# ghf_sensor.net
KiCad netlist of a schematic drawn in EAGLE
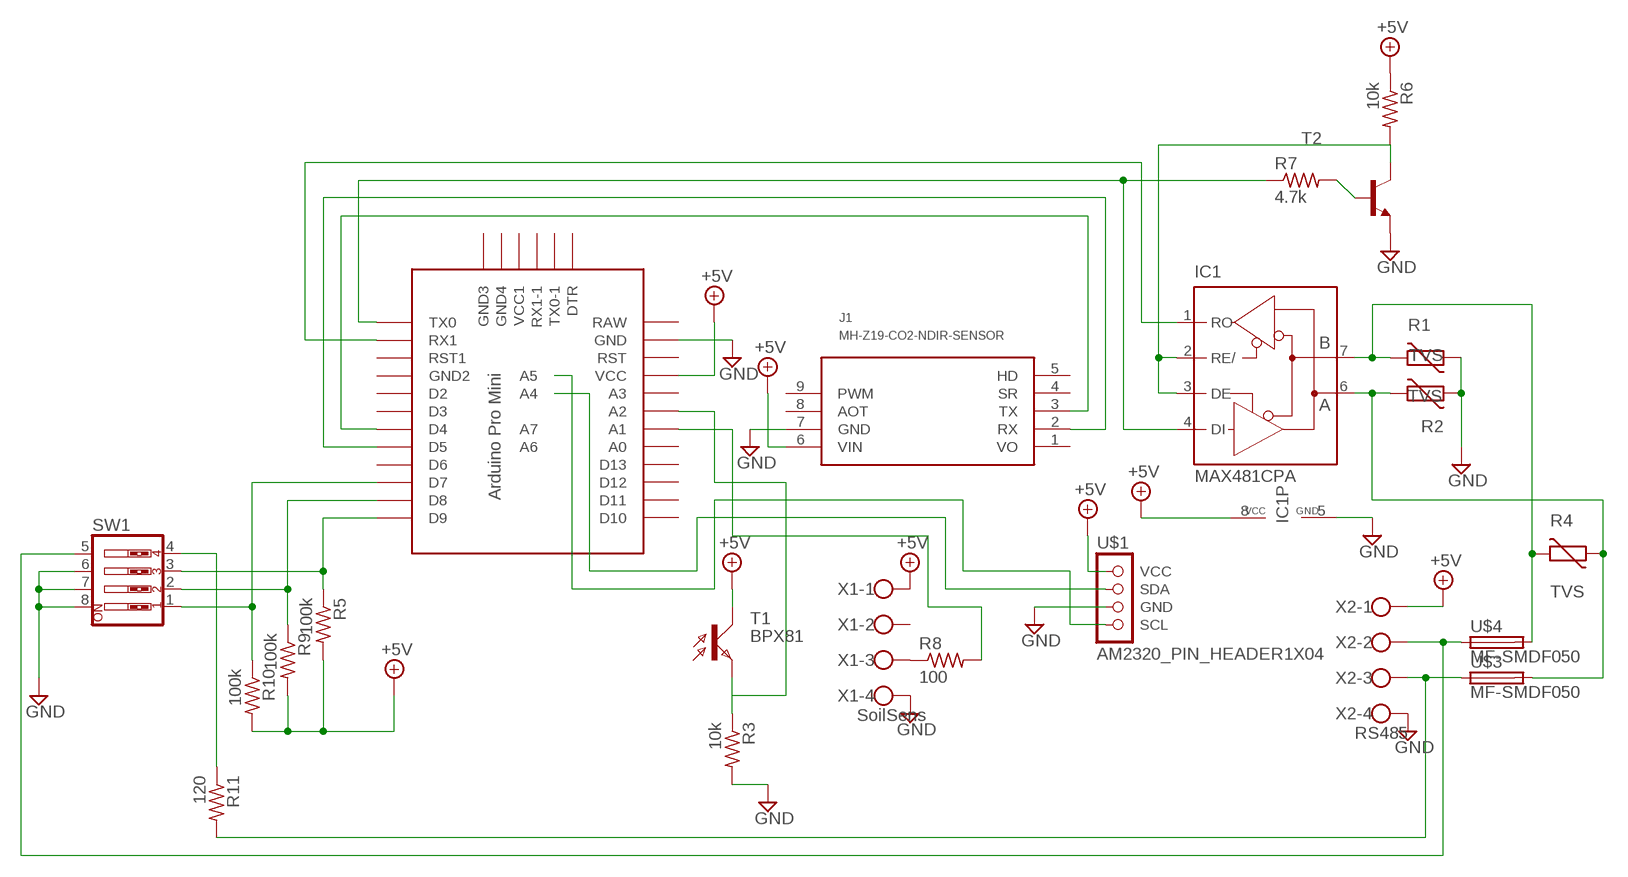
[diagram p0: schematic, sheet 1]

(export (version "E")
  (design (tool "Eeschema 10.0.6"))
  (components
    (comp (ref "IC1")
      (value "MAX481CPA")
      (footprint "eagle-import:DIL08")
      (libsource (lib "eagle-import") (part "MAX481CPA"))
    )
    (comp (ref "J1")
      (value "MH-Z19-CO2-NDIR-SENSOR")
      (footprint "eagle-import:MH-Z19")
      (libsource (lib "eagle-import") (part "MH-Z19-CO2-NDIR-SENSOR"))
    )
    (comp (ref "R1")
      (value "TVS")
      (footprint "eagle-import:CT_CN1812")
      (libsource (lib "eagle-import") (part "VARISTORCN1812"))
    )
    (comp (ref "R2")
      (value "TVS")
      (footprint "eagle-import:CT_CN1812")
      (libsource (lib "eagle-import") (part "VARISTORCN1812"))
    )
    (comp (ref "R3")
      (value "10k")
      (footprint "eagle-import:0204_5")
      (libsource (lib "eagle-import") (part "R-US_0204/5"))
    )
    (comp (ref "R4")
      (value "TVS")
      (footprint "eagle-import:CT_CN1812")
      (libsource (lib "eagle-import") (part "VARISTORCN1812"))
    )
    (comp (ref "R5")
      (value "100k")
      (footprint "eagle-import:0204V")
      (libsource (lib "eagle-import") (part "R-US_0204/2V"))
    )
    (comp (ref "R6")
      (value "10k")
      (footprint "eagle-import:0204_5")
      (libsource (lib "eagle-import") (part "R-US_0204/5"))
    )
    (comp (ref "R7")
      (value "4.7k")
      (footprint "eagle-import:0204_5")
      (libsource (lib "eagle-import") (part "R-US_0204/5"))
    )
    (comp (ref "R8")
      (value "100")
      (footprint "eagle-import:0204_5")
      (libsource (lib "eagle-import") (part "R-US_0204/5"))
    )
    (comp (ref "R9")
      (value "100k")
      (footprint "eagle-import:0204V")
      (libsource (lib "eagle-import") (part "R-US_0204/2V"))
    )
    (comp (ref "R10")
      (value "100k")
      (footprint "eagle-import:0204V")
      (libsource (lib "eagle-import") (part "R-US_0204/2V"))
    )
    (comp (ref "R11")
      (value "120")
      (footprint "eagle-import:0204V")
      (libsource (lib "eagle-import") (part "R-US_0204/2V"))
    )
    (comp (ref "SW1")
      (value "SW_DIP-4")
      (footprint "eagle-import:EDG-04")
      (libsource (lib "eagle-import") (part "SW_DIP-4"))
    )
    (comp (ref "T1")
      (value "BPX81")
      (footprint "eagle-import:BPX81")
      (libsource (lib "eagle-import") (part "BPX81"))
    )
    (comp (ref "T2")
      (value "-NPN-TO92-ECB")
      (footprint "eagle-import:TO92-ECB")
      (libsource (lib "eagle-import") (part "-NPN-TO92-ECB"))
    )
    (comp (ref "U$1")
      (value "AM2320_PIN_HEADER1X04")
      (footprint "eagle-import:1X04")
      (libsource (lib "eagle-import") (part "AM2320_PIN_HEADER1X04"))
    )
    (comp (ref "U$2")
      (value "PRO-MINI-2")
      (footprint "eagle-import:PRO-MINI-2")
      (libsource (lib "eagle-import") (part "PRO-MINI-2"))
    )
    (comp (ref "U$3")
      (value "MF-SMDF050")
      (footprint "eagle-import:MF-SMDF050")
      (libsource (lib "eagle-import") (part "MF-SMDF050"))
    )
    (comp (ref "U$4")
      (value "MF-SMDF050")
      (footprint "eagle-import:MF-SMDF050")
      (libsource (lib "eagle-import") (part "MF-SMDF050"))
    )
    (comp (ref "X1")
      (value "SoilSens")
      (footprint "eagle-import:W237-4")
      (libsource (lib "eagle-import") (part "W237-4"))
    )
    (comp (ref "X2")
      (value "RS485")
      (footprint "eagle-import:W237-4")
      (libsource (lib "eagle-import") (part "W237-4"))
    )
  )
  (nets
    (net (code "1") (name "+5V") (class "Default")
      (node (ref "IC1") (pin "8") (pinfunction "VCC_8") (pintype "power_in"))
      (node (ref "J1") (pin "6") (pinfunction "VIN_6") (pintype "power_in"))
      (node (ref "R10") (pin "2") (pinfunction "2_2") (pintype "passive"))
      (node (ref "R5") (pin "2") (pinfunction "2_2") (pintype "passive"))
      (node (ref "R6") (pin "1") (pinfunction "1_1") (pintype "passive"))
      (node (ref "R9") (pin "2") (pinfunction "2_2") (pintype "passive"))
      (node (ref "T1") (pin "C") (pinfunction "C_C") (pintype "passive"))
      (node (ref "U$1") (pin "1") (pinfunction "VCC_1") (pintype "passive"))
      (node (ref "U$2") (pin "VCC") (pinfunction "VCC_VCC") (pintype "bidirectional"))
      (node (ref "X1") (pin "1") (pinfunction "KL_1") (pintype "passive"))
      (node (ref "X2") (pin "1") (pinfunction "KL_1") (pintype "passive"))
    )
    (net (code "2") (name "/VO") (class "Default")
      (node (ref "J1") (pin "1") (pinfunction "VO_1") (pintype "power_in"))
    )
    (net (code "3") (name "GND") (class "Default")
      (node (ref "IC1") (pin "5") (pinfunction "GND_5") (pintype "power_in"))
      (node (ref "J1") (pin "7") (pinfunction "GND_7") (pintype "power_in"))
      (node (ref "R1") (pin "1") (pinfunction "1_1") (pintype "passive"))
      (node (ref "R2") (pin "2") (pinfunction "2_2") (pintype "passive"))
      (node (ref "R3") (pin "2") (pinfunction "2_2") (pintype "passive"))
      (node (ref "SW1") (pin "6") (pinfunction "6_6") (pintype "passive"))
      (node (ref "SW1") (pin "7") (pinfunction "7_7") (pintype "passive"))
      (node (ref "SW1") (pin "8") (pinfunction "8_8") (pintype "passive"))
      (node (ref "T2") (pin "E") (pinfunction "E_E") (pintype "passive"))
      (node (ref "U$1") (pin "3") (pinfunction "GND_3") (pintype "passive"))
      (node (ref "U$2") (pin "GND") (pinfunction "GND_GND") (pintype "bidirectional"))
      (node (ref "X1") (pin "4") (pinfunction "KL_4") (pintype "passive"))
      (node (ref "X2") (pin "4") (pinfunction "KL_4") (pintype "passive"))
    )
    (net (code "4") (name "Net-(IC1A-A)") (class "Default")
      (node (ref "IC1") (pin "6") (pinfunction "A_6") (pintype "passive"))
      (node (ref "R2") (pin "1") (pinfunction "1_1") (pintype "passive"))
      (node (ref "R4") (pin "1") (pinfunction "1_1") (pintype "passive"))
      (node (ref "U$3") (pin "2") (pinfunction "2_2") (pintype "passive"))
    )
    (net (code "5") (name "Net-(IC1A-B)") (class "Default")
      (node (ref "IC1") (pin "7") (pinfunction "B_7") (pintype "passive"))
      (node (ref "R1") (pin "2") (pinfunction "2_2") (pintype "passive"))
      (node (ref "R4") (pin "2") (pinfunction "2_2") (pintype "passive"))
      (node (ref "U$4") (pin "2") (pinfunction "2_2") (pintype "passive"))
    )
    (net (code "6") (name "Net-(IC1A-DE)") (class "Default")
      (node (ref "IC1") (pin "2") (pinfunction "RE/_2") (pintype "input"))
      (node (ref "IC1") (pin "3") (pinfunction "DE_3") (pintype "input"))
      (node (ref "R6") (pin "2") (pinfunction "2_2") (pintype "passive"))
      (node (ref "T2") (pin "C") (pinfunction "C_C") (pintype "passive"))
    )
    (net (code "7") (name "Net-(IC1A-DI)") (class "Default")
      (node (ref "IC1") (pin "4") (pinfunction "DI_4") (pintype "input"))
      (node (ref "R7") (pin "1") (pinfunction "1_1") (pintype "passive"))
      (node (ref "U$2") (pin "TX0") (pinfunction "TX0_TX0") (pintype "bidirectional"))
    )
    (net (code "8") (name "Net-(IC1A-RO)") (class "Default")
      (node (ref "IC1") (pin "1") (pinfunction "RO_1") (pintype "output"))
      (node (ref "U$2") (pin "RX1") (pinfunction "RX1_RX1") (pintype "bidirectional"))
    )
    (net (code "9") (name "Net-(J1-RX)") (class "Default")
      (node (ref "J1") (pin "2") (pinfunction "RX_2") (pintype "input"))
      (node (ref "U$2") (pin "D5") (pinfunction "D5_D5") (pintype "bidirectional"))
    )
    (net (code "10") (name "Net-(J1-TX)") (class "Default")
      (node (ref "J1") (pin "3") (pinfunction "TX_3") (pintype "output"))
      (node (ref "U$2") (pin "D4") (pinfunction "D4_D4") (pintype "bidirectional"))
    )
    (net (code "11") (name "Net-(R3-Pad1)") (class "Default")
      (node (ref "R3") (pin "1") (pinfunction "1_1") (pintype "passive"))
      (node (ref "T1") (pin "E") (pinfunction "E_E") (pintype "passive"))
      (node (ref "U$2") (pin "A2") (pinfunction "A2_A2") (pintype "bidirectional"))
    )
    (net (code "12") (name "Net-(R5-Pad1)") (class "Default")
      (node (ref "R5") (pin "1") (pinfunction "1_1") (pintype "passive"))
      (node (ref "SW1") (pin "3") (pinfunction "3_3") (pintype "passive"))
      (node (ref "U$2") (pin "D9") (pinfunction "D9_D9") (pintype "bidirectional"))
    )
    (net (code "13") (name "Net-(R7-Pad2)") (class "Default")
      (node (ref "R7") (pin "2") (pinfunction "2_2") (pintype "passive"))
      (node (ref "T2") (pin "B") (pinfunction "B_B") (pintype "passive"))
    )
    (net (code "14") (name "Net-(R8-Pad2)") (class "Default")
      (node (ref "R8") (pin "2") (pinfunction "2_2") (pintype "passive"))
      (node (ref "U$2") (pin "A1") (pinfunction "A1_A1") (pintype "bidirectional"))
    )
    (net (code "15") (name "Net-(R9-Pad1)") (class "Default")
      (node (ref "R9") (pin "1") (pinfunction "1_1") (pintype "passive"))
      (node (ref "SW1") (pin "2") (pinfunction "2_2") (pintype "passive"))
      (node (ref "U$2") (pin "D8") (pinfunction "D8_D8") (pintype "bidirectional"))
    )
    (net (code "16") (name "Net-(R10-Pad1)") (class "Default")
      (node (ref "R10") (pin "1") (pinfunction "1_1") (pintype "passive"))
      (node (ref "SW1") (pin "1") (pinfunction "1_1") (pintype "passive"))
      (node (ref "U$2") (pin "D7") (pinfunction "D7_D7") (pintype "bidirectional"))
    )
    (net (code "17") (name "Net-(R11-Pad1)") (class "Default")
      (node (ref "R11") (pin "1") (pinfunction "1_1") (pintype "passive"))
      (node (ref "SW1") (pin "4") (pinfunction "4_4") (pintype "passive"))
    )
    (net (code "18") (name "Net-(U$1-SCL)") (class "Default")
      (node (ref "U$1") (pin "4") (pinfunction "SCL_4") (pintype "passive"))
      (node (ref "U$2") (pin "A5") (pinfunction "A5_A5") (pintype "bidirectional"))
    )
    (net (code "19") (name "Net-(U$1-SDA)") (class "Default")
      (node (ref "U$1") (pin "2") (pinfunction "SDA_2") (pintype "passive"))
      (node (ref "U$2") (pin "A4") (pinfunction "A4_A4") (pintype "bidirectional"))
    )
    (net (code "20") (name "Net-(X1C-KL)") (class "Default")
      (node (ref "R8") (pin "1") (pinfunction "1_1") (pintype "passive"))
      (node (ref "X1") (pin "3") (pinfunction "KL_3") (pintype "passive"))
    )
    (net (code "21") (name "Net-(X2B-KL)") (class "Default")
      (node (ref "SW1") (pin "5") (pinfunction "5_5") (pintype "passive"))
      (node (ref "U$4") (pin "1") (pinfunction "1_1") (pintype "passive"))
      (node (ref "X2") (pin "2") (pinfunction "KL_2") (pintype "passive"))
    )
    (net (code "22") (name "Net-(X2C-KL)") (class "Default")
      (node (ref "R11") (pin "2") (pinfunction "2_2") (pintype "passive"))
      (node (ref "U$3") (pin "1") (pinfunction "1_1") (pintype "passive"))
      (node (ref "X2") (pin "3") (pinfunction "KL_3") (pintype "passive"))
    )
    (net (code "23") (name "unconnected-(J1-AOT-Pad8)") (class "Default")
      (node (ref "J1") (pin "8") (pinfunction "AOT_8") (pintype "no_connect"))
    )
    (net (code "24") (name "unconnected-(J1-HD-Pad5)") (class "Default")
      (node (ref "J1") (pin "5") (pinfunction "HD_5") (pintype "input"))
    )
    (net (code "25") (name "unconnected-(J1-PWM-Pad9)") (class "Default")
      (node (ref "J1") (pin "9") (pinfunction "PWM_9") (pintype "output"))
    )
    (net (code "26") (name "unconnected-(J1-SR-Pad4)") (class "Default")
      (node (ref "J1") (pin "4") (pinfunction "SR_4") (pintype "no_connect"))
    )
    (net (code "27") (name "unconnected-(U$2-GND2-PadGND1)") (class "Default")
      (node (ref "U$2") (pin "GND1") (pinfunction "GND2_GND1") (pintype "bidirectional"))
    )
    (net (code "28") (name "unconnected-(U$2-GND3-PadGND2)") (class "Default")
      (node (ref "U$2") (pin "GND2") (pinfunction "GND3_GND2") (pintype "bidirectional"))
    )
    (net (code "29") (name "unconnected-(U$2-GND4-PadGND3)") (class "Default")
      (node (ref "U$2") (pin "GND3") (pinfunction "GND4_GND3") (pintype "bidirectional"))
    )
    (net (code "30") (name "unconnected-(U$2-PadA0)") (class "Default")
      (node (ref "U$2") (pin "A0") (pinfunction "A0_A0") (pintype "bidirectional"))
    )
    (net (code "31") (name "unconnected-(U$2-PadA3)") (class "Default")
      (node (ref "U$2") (pin "A3") (pinfunction "A3_A3") (pintype "bidirectional"))
    )
    (net (code "32") (name "unconnected-(U$2-PadA6)") (class "Default")
      (node (ref "U$2") (pin "A6") (pinfunction "A6_A6") (pintype "bidirectional"))
    )
    (net (code "33") (name "unconnected-(U$2-PadA7)") (class "Default")
      (node (ref "U$2") (pin "A7") (pinfunction "A7_A7") (pintype "bidirectional"))
    )
    (net (code "34") (name "unconnected-(U$2-PadD2)") (class "Default")
      (node (ref "U$2") (pin "D2") (pinfunction "D2_D2") (pintype "bidirectional"))
    )
    (net (code "35") (name "unconnected-(U$2-PadD3)") (class "Default")
      (node (ref "U$2") (pin "D3") (pinfunction "D3_D3") (pintype "bidirectional"))
    )
    (net (code "36") (name "unconnected-(U$2-PadD6)") (class "Default")
      (node (ref "U$2") (pin "D6") (pinfunction "D6_D6") (pintype "bidirectional"))
    )
    (net (code "37") (name "unconnected-(U$2-PadD10)") (class "Default")
      (node (ref "U$2") (pin "D10") (pinfunction "D10_D10") (pintype "bidirectional"))
    )
    (net (code "38") (name "unconnected-(U$2-PadD11)") (class "Default")
      (node (ref "U$2") (pin "D11") (pinfunction "D11_D11") (pintype "bidirectional"))
    )
    (net (code "39") (name "unconnected-(U$2-PadD12)") (class "Default")
      (node (ref "U$2") (pin "D12") (pinfunction "D12_D12") (pintype "bidirectional"))
    )
    (net (code "40") (name "unconnected-(U$2-PadD13)") (class "Default")
      (node (ref "U$2") (pin "D13") (pinfunction "D13_D13") (pintype "bidirectional"))
    )
    (net (code "41") (name "unconnected-(U$2-PadDTR)") (class "Default")
      (node (ref "U$2") (pin "DTR") (pinfunction "DTR_DTR") (pintype "bidirectional"))
    )
    (net (code "42") (name "unconnected-(U$2-PadRAW)") (class "Default")
      (node (ref "U$2") (pin "RAW") (pinfunction "RAW_RAW") (pintype "bidirectional"))
    )
    (net (code "43") (name "unconnected-(U$2-PadRST)") (class "Default")
      (node (ref "U$2") (pin "RST") (pinfunction "RST_RST") (pintype "bidirectional"))
    )
    (net (code "44") (name "unconnected-(U$2-PadRST1)") (class "Default")
      (node (ref "U$2") (pin "RST1") (pinfunction "RST1_RST1") (pintype "bidirectional"))
    )
    (net (code "45") (name "unconnected-(U$2-PadRX1-1)") (class "Default")
      (node (ref "U$2") (pin "RX1-1") (pinfunction "RX1-1_RX1-1") (pintype "bidirectional"))
    )
    (net (code "46") (name "unconnected-(U$2-PadTX0-1)") (class "Default")
      (node (ref "U$2") (pin "TX0-1") (pinfunction "TX0-1_TX0-1") (pintype "bidirectional"))
    )
    (net (code "47") (name "unconnected-(U$2-PadVCC1)") (class "Default")
      (node (ref "U$2") (pin "VCC1") (pinfunction "VCC1_VCC1") (pintype "bidirectional"))
    )
    (net (code "48") (name "unconnected-(X1B-KL-Pad2)") (class "Default")
      (node (ref "X1") (pin "2") (pinfunction "KL_2") (pintype "passive"))
    )
  )
)
